# EEPROM.net
KiCad netlist of a schematic drawn in Altium Designer
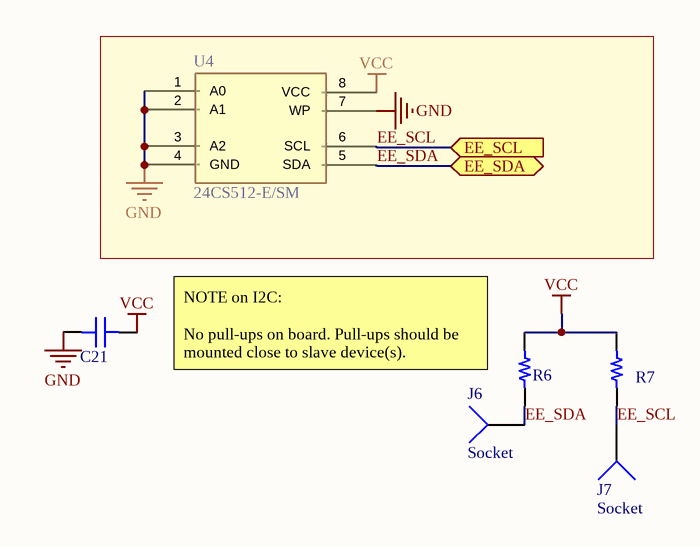
[diagram p0: EEPROM.SchDoc]

(export (version "E")
  (design (tool "Eeschema 10.0.6"))
  (components
    (comp (ref "C21")
      (value "C0805C104M5RAC7025")
      (footprint "CAP SMD 0805")
      (description "0.1 µF ±20% 50V Ceramic Capacitor X7R 0805 (2012 Metric)")
      (libsource (lib "REMOTE RGBW CONTROLLER") (part "CAPACITOR X7R"))
    )
    (comp (ref "J6")
      (value "Socket")
      (footprint "PIN1")
      (fields (field (name "PUBLISHER") "Altium Limited"))
      (libsource (lib "Miscellaneous Connectors") (part "Socket"))
    )
    (comp (ref "J7")
      (value "Socket")
      (footprint "PIN1")
      (fields (field (name "PUBLISHER") "Altium Limited"))
      (libsource (lib "Miscellaneous Connectors") (part "Socket"))
    )
    (comp (ref "R6")
      (value "10K")
      (footprint "RES SMD 0805")
      (description "RES SMD 10K OHM 1% 1/4W 0805")
      (libsource (lib "DIY-USB Led Controller") (part "RESISTOR"))
    )
    (comp (ref "R7")
      (value "10K")
      (footprint "RES SMD 0805")
      (description "RES SMD 10K OHM 1% 1/4W 0805")
      (libsource (lib "DIY-USB Led Controller") (part "RESISTOR"))
    )
    (comp (ref "U4")
      (value "24CS512-E/SM")
      (footprint "21-0041B_8")
      (description "EEPROM Memory IC 512Kb (64K x 8) I²C 3.4 MHz 400 ns 8-SOIJ")
      (libsource (lib "Prcesion Agriculture_5") (part "AT24CW16X/24CW32X/24CW64X"))
    )
  )
  (nets
    (net (code "1") (name "/EE_SCL") (class "Default")
      (node (ref "J7") (pin "1") (pinfunction "1_1") (pintype "passive"))
      (node (ref "R7") (pin "1") (pinfunction "1_1") (pintype "passive"))
      (node (ref "U4") (pin "6") (pinfunction "SCL_6") (pintype "passive"))
    )
    (net (code "2") (name "/EE_SDA") (class "Default")
      (node (ref "J6") (pin "1") (pinfunction "1_1") (pintype "passive"))
      (node (ref "R6") (pin "1") (pinfunction "1_1") (pintype "passive"))
      (node (ref "U4") (pin "5") (pinfunction "SDA_5") (pintype "passive"))
    )
    (net (code "3") (name "GND") (class "Default")
      (node (ref "C21") (pin "1") (pinfunction "1_1") (pintype "passive"))
      (node (ref "U4") (pin "1") (pinfunction "A0_1") (pintype "passive"))
      (node (ref "U4") (pin "2") (pinfunction "A1_2") (pintype "passive"))
      (node (ref "U4") (pin "3") (pinfunction "A2_3") (pintype "power_in"))
      (node (ref "U4") (pin "4") (pinfunction "GND_4") (pintype "power_in"))
      (node (ref "U4") (pin "7") (pinfunction "WP_7") (pintype "passive"))
    )
    (net (code "4") (name "VCC") (class "Default")
      (node (ref "C21") (pin "2") (pinfunction "2_2") (pintype "passive"))
      (node (ref "R6") (pin "2") (pinfunction "2_2") (pintype "passive"))
      (node (ref "R7") (pin "2") (pinfunction "2_2") (pintype "passive"))
      (node (ref "U4") (pin "8") (pinfunction "VCC_8") (pintype "power_in"))
    )
  )
)
